# AQM_with_esp32.net
KiCad netlist of a schematic drawn in Altium Designer
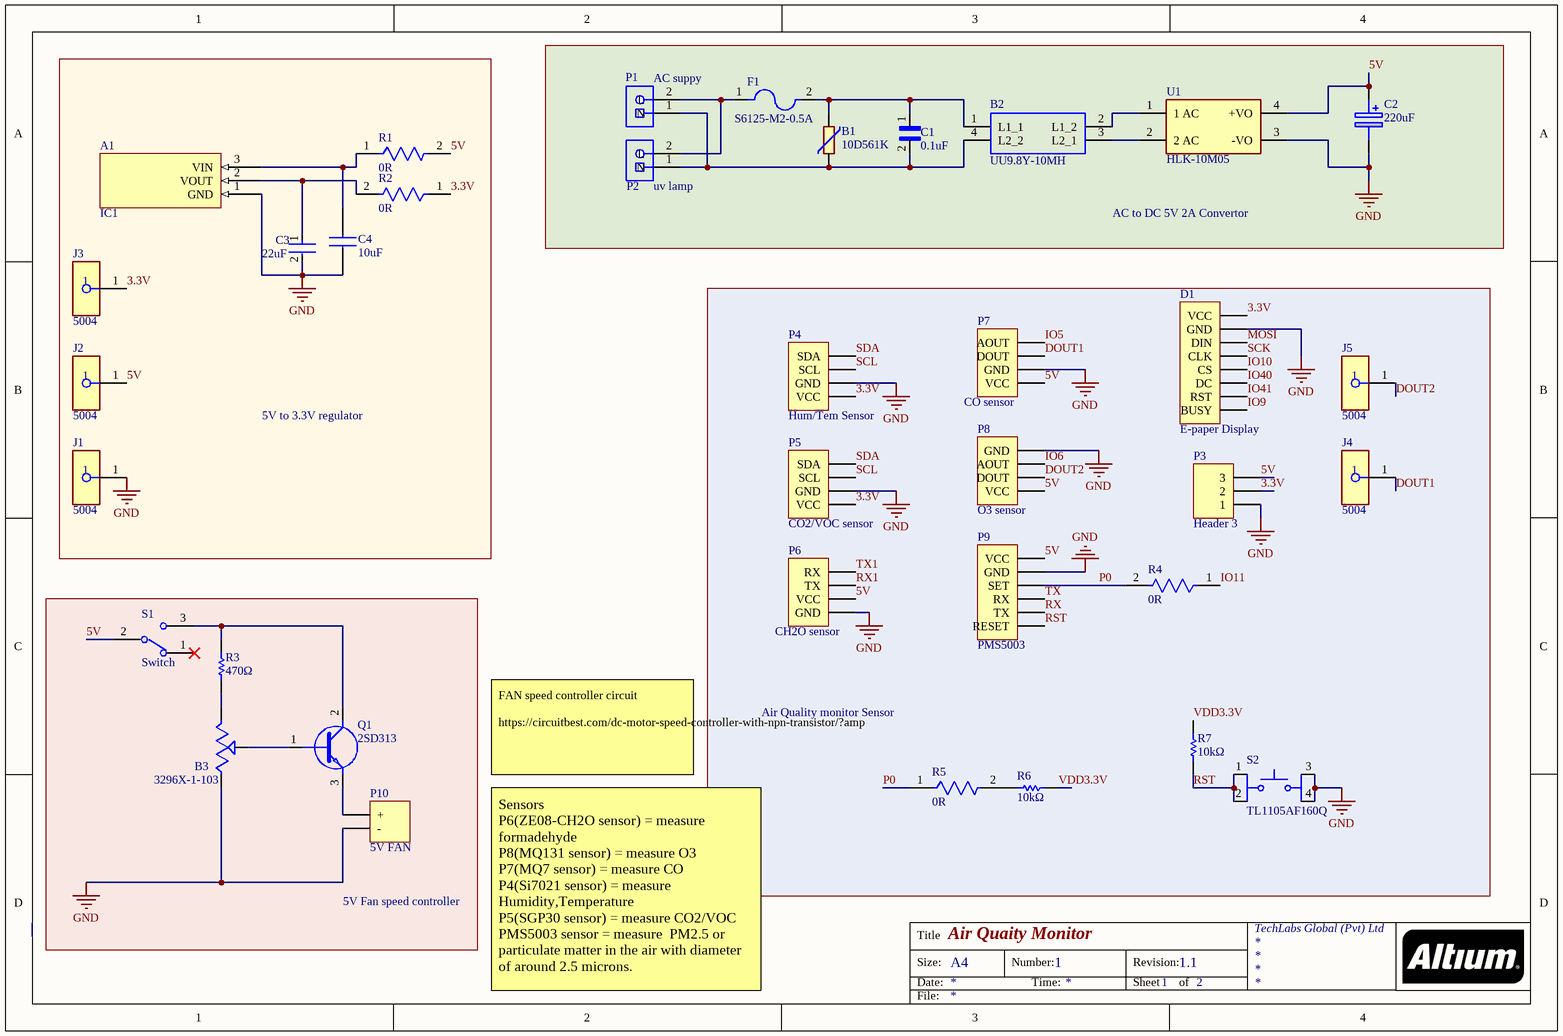
[diagram p0: AQM with esp32.SchDoc]

(export (version "E")
  (design (tool "Eeschema 10.0.6"))
  (components
    (comp (ref "A1")
      (value "IC1")
      (footprint "SOT89-150P350X150-3N")
      (fields
        (field (name "MANUFACTURER") "YONGYUTAI")
        (field (name "MFR. PART #") "AMS1117-3.3")
        (field (name "LCSC PART #") "C2904742")
      )
      (libsource (lib "AMS1117-3.3") (part "IC?"))
    )
    (comp (ref "B1")
      (value "10D561K")
      (footprint "10D561K")
      (description "920V 42.3J 180pF@1kHz 460V 350V 504V~616V 2.5kA Plugin Varistors ROHS")
      (fields (field (name "LCSC PART #") "C113236") (field (name "MANUFACTURER") "Hongzhi Elec"))
      (libsource (lib "10D561K") (part "10D561K"))
    )
    (comp (ref "B2")
      (value "UU9.8Y-10MH")
      (footprint "UU98Y10MH")
      (description "10mH@1kHz 1.2Ω 2 500mA 50V Plugin Common Mode Filters ROHS")
      (fields
        (field (name "MANUFACTURER") "FH (Guangdong Fenghua Advanced Tech)")
        (field (name "LCSC PART #") "C75192")
      )
      (libsource (lib "UU9.8Y-10MH") (part "UU9.8Y-10MH"))
    )
    (comp (ref "B3")
      (value "3296X-1-103")
      (footprint "3296X1223LF")
      (description "±10% 10kΩ Plugin Variable Resistors/Potentiometers ROHS")
      (fields
        (field (name "LCSC PART #") "C118955")
        (field (name "MANUFACTURER") "BOCHEN(Chengdu Guosheng Tech)")
      )
      (libsource (lib "3296X-1-103") (part "3296X-1-103"))
    )
    (comp (ref "C1")
      (value "0.1uF")
      (footprint "MPX-104K275VAC-C-D2")
      (description "X2 100nF ±10% 275V Plugin,P=15mm Suppression Capacitors ROHS")
      (fields (field (name "LCSC PART #") "C914484") (field (name "MANUFACTURER") "NDF"))
      (libsource (lib "X2-104K-275VAC") (part "MPX-104K275VAC-C-D2"))
    )
    (comp (ref "C2")
      (value "220uF")
      (footprint "CAPAE830X1050N")
      (fields
        (field (name "MANUFACTURER") "Nichicon")
        (field (name "MFR. PART #") "UUR1C221MNL1GS")
        (field (name "LCSC PART #") "C445237")
      )
      (libsource (lib "UUR1C221MNL1GS") (part "UUR1C221MNL1GS"))
    )
    (comp (ref "C3")
      (value "22uF")
      (footprint "FP-GRM219-0_2-0_15-IPC_A")
      (description "Chip Multilayer Ceramic Capacitors for General Purpose, 0805, 22uF, X5R, 15%, 20%, 16V")
      (fields (field (name "MFR. PART #") "GRM219R61C226ME15L") (field (name "LCSC PART #") "C162295"))
      (libsource (lib "Altium Content Vault") (part "b4654b650e69147ec39a6b967a45e02"))
    )
    (comp (ref "C4")
      (value "10uF")
      (footprint "CL05A106MQ5NUNC")
      (description "6.3V 10uF X5R ±20% 0402 Multilayer Ceramic Capacitors MLCC - SMD/SMT ROHS")
      (fields
        (field (name "MANUFACTURER") "Samsung Electro-Mechanics")
        (field (name "MFR. PART #") "CL05A106MQ5NUNC")
      )
      (libsource (lib "CL05A106MQ5NUNC") (part "CL05A106MQ5NUNC"))
    )
    (comp (ref "D1")
      (value "E-paper Display")
      (footprint "HDR1X8")
      (description "Header, 8-Pin")
      (fields (field (name "PUBLISHER") "Altium Limited"))
      (libsource (lib "Miscellaneous Connectors") (part "Header 8"))
    )
    (comp (ref "F1")
      (value "S6125-M2-0.5A")
      (footprint "CAPC6125X25N")
      (description "SMD Fuses ROHS")
      (fields (field (name "LCSC PART #") "C845172") (field (name "MANUFACTURER") "SART(Nanjing Sart Tech)"))
      (libsource (lib "S6125-M2-0.5A") (part "S6125-M2-0.5A"))
    )
    (comp (ref "J1")
      (value "5004")
      (footprint "FP-5004-MFG")
      (description "PC TEST POINT MINIATURE YELLOW")
      (fields (field (name "MANUFACTURER") "Keystone") (field (name "LCSC PART #") "C2906762"))
      (libsource (lib "Altium Content Vault") (part "98815daf2f2c152b0c43f5ab9800df6"))
    )
    (comp (ref "J2")
      (value "5004")
      (footprint "FP-5004-MFG")
      (description "PC TEST POINT MINIATURE YELLOW")
      (fields (field (name "MANUFACTURER") "Keystone") (field (name "LCSC PART #") "C2906762"))
      (libsource (lib "Altium Content Vault") (part "98815daf2f2c152b0c43f5ab9800df6"))
    )
    (comp (ref "J3")
      (value "5004")
      (footprint "FP-5004-MFG")
      (description "PC TEST POINT MINIATURE YELLOW")
      (fields (field (name "MANUFACTURER") "Keystone") (field (name "LCSC PART #") "C2906762"))
      (libsource (lib "Altium Content Vault") (part "98815daf2f2c152b0c43f5ab9800df6"))
    )
    (comp (ref "J4")
      (value "5004")
      (footprint "FP-5004-MFG")
      (description "PC TEST POINT MINIATURE YELLOW")
      (fields (field (name "MANUFACTURER") "Keystone") (field (name "LCSC PART #") "C2906762"))
      (libsource (lib "Altium Content Vault") (part "98815daf2f2c152b0c43f5ab9800df6"))
    )
    (comp (ref "J5")
      (value "5004")
      (footprint "FP-5004-MFG")
      (description "PC TEST POINT MINIATURE YELLOW")
      (fields (field (name "MANUFACTURER") "Keystone") (field (name "LCSC PART #") "C2906762"))
      (libsource (lib "Altium Content Vault") (part "98815daf2f2c152b0c43f5ab9800df6"))
    )
    (comp (ref "P1")
      (value "AC suppy")
      (footprint "PHOE-1729128-2_V")
      (description "13.5A 400V Green Straight pin 5.08mm 1 2 Plugin,P=5.08mm Screw terminal ROHS")
      (fields (field (name "MFR. PART #") "1729128") (field (name "LCSC PART #") "C91153"))
      (libsource (lib "Altium Content Vault") (part "CN-2P-F-R2"))
    )
    (comp (ref "P2")
      (value "uv lamp")
      (footprint "PHOE-1729128-2_V")
      (description "13.5A 400V Green Straight pin 5.08mm 1 2 Plugin,P=5.08mm Screw terminal ROHS")
      (fields (field (name "MFR. PART #") "1729128") (field (name "LCSC PART #") "C91153"))
      (libsource (lib "Altium Content Vault") (part "CN-2P-F-R2"))
    )
    (comp (ref "P3")
      (value "Header 3")
      (footprint "HDR1X3")
      (description "Header, 3-Pin")
      (fields (field (name "PUBLISHER") "Altium Limited"))
      (libsource (lib "Miscellaneous Connectors") (part "Header 3"))
    )
    (comp (ref "P4")
      (value "Hum/Tem Sensor")
      (footprint "HDR1X4")
      (description "Si7021 Header, 4-Pin")
      (libsource (lib "Miscellaneous Connectors") (part "Header 4"))
    )
    (comp (ref "P5")
      (value "CO2/VOC sensor")
      (footprint "HDR1X4")
      (description "SGP30 Header, 4-Pin")
      (fields (field (name "PUBLISHER") "Altium Limited"))
      (libsource (lib "Miscellaneous Connectors") (part "Header 4"))
    )
    (comp (ref "P6")
      (value "CH2O sensor")
      (footprint "HDR1X4")
      (description "- Sensor Modules ROHS")
      (fields
        (field (name "MFR. PART #") "ZE08-CH2O")
        (field (name "MANUFACTURER") "Zhengzhou Winsen Elec Tech")
      )
      (libsource (lib "") (part "Header 4_1"))
    )
    (comp (ref "P7")
      (value "CO sensor")
      (footprint "HDR1X4")
      (description "MQ7 Header, 4-Pin")
      (fields (field (name "PUBLISHER") "Altium Limited"))
      (libsource (lib "") (part "Header 4_2"))
    )
    (comp (ref "P8")
      (value "O3 sensor")
      (footprint "HDR1X4")
      (description "MQ131 Header, 4-Pin")
      (fields (field (name "PUBLISHER") "Altium Limited"))
      (libsource (lib "") (part "Header 4_3"))
    )
    (comp (ref "P9")
      (value "PMS5003")
      (footprint "HDR1X6")
      (description "PMS5003 Sensor Modules ROHS")
      (fields (field (name "LCSC PART #") "C91431") (field (name "MANUFACTURER") "Beijing Plantower"))
      (libsource (lib "Miscellaneous Connectors") (part "Header 6"))
    )
    (comp (ref "P10")
      (value "5V FAN")
      (footprint "HDR1X2")
      (description "Header, 2-Pin")
      (fields (field (name "PUBLISHER") "Altium Limited"))
      (libsource (lib "Miscellaneous Connectors") (part "Header 2"))
    )
    (comp (ref "Q1")
      (value "2SD313")
      (footprint "TO304P498X1010X2089-3P")
      (description "NPN Transistor, TO-220")
      (fields
        (field (name "LCSC PART #") "C3031919")
        (field (name "MANUFACTURER") "Jiangsu Changjing Electronics Technology Co., Ltd.")
      )
      (libsource (lib "2SD313") (part "2SD313"))
    )
    (comp (ref "R1")
      (value "0R")
      (footprint "FP-RC0402-0_4-IPC_A")
      (description "RES SMD 0 OHM JUMPER 1/16W 0402")
      (fields (field (name "MANUFACTURER") "Yageo") (field (name "LCSC PART #") "C106231"))
      (libsource (lib "Altium Content Vault") (part "1029c3af85768c4190bb7ad29bc67b5"))
    )
    (comp (ref "R2")
      (value "0R")
      (footprint "FP-RC0402-0_4-IPC_A")
      (description "RES SMD 0 OHM JUMPER 1/16W 0402")
      (fields (field (name "MANUFACTURER") "Yageo") (field (name "LCSC PART #") "C106231"))
      (libsource (lib "Altium Content Vault") (part "1029c3af85768c4190bb7ad29bc67b5"))
    )
    (comp (ref "R3")
      (value "470Ω")
      (footprint "RESC1608X55X25LL10T15")
      (fields
        (field (name "LCSC PART #") "C114669")
        (field (name "MFR. PART #") "RC0603FR-07470RL")
        (field (name "MANUFACTURER") "YAGEO")
      )
      (libsource (lib "Altium Content Vault") (part "RES-2"))
    )
    (comp (ref "R4")
      (value "0R")
      (footprint "FP-RC0402-0_4-IPC_A")
      (description "RES SMD 0 OHM JUMPER 1/16W 0402")
      (fields (field (name "MANUFACTURER") "Yageo") (field (name "LCSC PART #") "C106231"))
      (libsource (lib "Altium Content Vault") (part "1029c3af85768c4190bb7ad29bc67b5"))
    )
    (comp (ref "R5")
      (value "0R")
      (footprint "FP-RC0402-0_4-IPC_A")
      (description "RES SMD 0 OHM JUMPER 1/16W 0402")
      (fields (field (name "MANUFACTURER") "Yageo") (field (name "LCSC PART #") "C106231"))
      (libsource (lib "Altium Content Vault") (part "1029c3af85768c4190bb7ad29bc67b5"))
    )
    (comp (ref "R6")
      (value "10kΩ")
      (footprint "RESC1005X40X25LL05T10")
      (fields
        (field (name "MFR. PART #") "RC0402FR-0710KL")
        (field (name "MANUFACTURER") "YAGEO")
        (field (name "LCSC PART #") "C60490")
      )
      (libsource (lib "Altium Content Vault") (part "RES"))
    )
    (comp (ref "R7")
      (value "10kΩ")
      (footprint "RESC1005X40X25LL05T10")
      (fields
        (field (name "MFR. PART #") "RC0402FR-0710KL")
        (field (name "MANUFACTURER") "YAGEO")
        (field (name "LCSC PART #") "C60490")
      )
      (libsource (lib "Altium Content Vault") (part "RES"))
    )
    (comp (ref "S1")
      (value "Switch")
      (footprint "SK3245SL1A")
      (fields
        (field (name "MANUFACTURER") "XKB Connectivity")
        (field (name "MFR. PART #") "SK-3245S-L1-A")
        (field (name "LCSC PART #") "C405951")
      )
      (libsource (lib "SK-3245S-L1-A") (part "SK-3245S-L1-A"))
    )
    (comp (ref "S2")
      (value "TL1105AF160Q")
      (footprint "TL1105AF160Q")
      (description "6mm 1.4mm Round Button 50mA Straight 6mm SPST 12V Plugin,6x6mm Tactile Switches ROHS")
      (fields (field (name "MANUFACTURER") "E-Switch") (field (name "LCSC PART #") "C273465"))
      (libsource (lib "TL1105AF160Q") (part "TL1105AF160Q"))
    )
    (comp (ref "U1")
      (value "HLK-10M05")
      (footprint "FP-HLK-10M05-MFG")
      (description "5V 2A 90VAC~265VAC 1 120V~350V Isolated Regulated 10W AC-DC 80% Plugin Power Modules ROHS")
      (fields (field (name "MANUFACTURER") "HI-LINK") (field (name "LCSC PART #") "C403745"))
      (libsource (lib "Altium Content Vault") (part "a65b17ccb3a75dffb3c3e849074403b"))
    )
  )
  (nets
    (net (code "1") (name "/3.3V") (class "Default")
      (node (ref "D1") (pin "8") (pinfunction "VCC_8") (pintype "passive"))
      (node (ref "J3") (pin "1") (pinfunction "1_1") (pintype "passive"))
      (node (ref "P3") (pin "2") (pinfunction "2_2") (pintype "passive"))
      (node (ref "P4") (pin "1") (pinfunction "VCC_1") (pintype "passive"))
      (node (ref "P5") (pin "1") (pinfunction "VCC_1") (pintype "passive"))
      (node (ref "R2") (pin "1") (pinfunction "1_1") (pintype "passive"))
    )
    (net (code "2") (name "/5V") (class "Default")
      (node (ref "C2") (pin "1") (pinfunction "+_1") (pintype "passive"))
      (node (ref "J2") (pin "1") (pinfunction "1_1") (pintype "passive"))
      (node (ref "P3") (pin "3") (pinfunction "3_3") (pintype "passive"))
      (node (ref "P6") (pin "2") (pinfunction "VCC_2") (pintype "passive"))
      (node (ref "P7") (pin "1") (pinfunction "VCC_1") (pintype "passive"))
      (node (ref "P8") (pin "1") (pinfunction "VCC_1") (pintype "passive"))
      (node (ref "P9") (pin "6") (pinfunction "VCC_6") (pintype "passive"))
      (node (ref "R1") (pin "2") (pinfunction "2_2") (pintype "passive"))
      (node (ref "S1") (pin "2") (pinfunction "2_2") (pintype "passive"))
      (node (ref "U1") (pin "4") (pinfunction "+VO_4") (pintype "power_in"))
    )
    (net (code "3") (name "/DOUT1") (class "Default")
      (node (ref "J4") (pin "1") (pinfunction "1_1") (pintype "passive"))
      (node (ref "P7") (pin "3") (pinfunction "DOUT_3") (pintype "passive"))
    )
    (net (code "4") (name "/DOUT2") (class "Default")
      (node (ref "J5") (pin "1") (pinfunction "1_1") (pintype "passive"))
      (node (ref "P8") (pin "2") (pinfunction "DOUT_2") (pintype "passive"))
    )
    (net (code "5") (name "/IO5") (class "Default")
      (node (ref "P7") (pin "4") (pinfunction "AOUT_4") (pintype "passive"))
    )
    (net (code "6") (name "/IO6") (class "Default")
      (node (ref "P8") (pin "3") (pinfunction "AOUT_3") (pintype "passive"))
    )
    (net (code "7") (name "/IO9") (class "Default")
      (node (ref "D1") (pin "1") (pinfunction "BUSY_1") (pintype "passive"))
    )
    (net (code "8") (name "/IO10") (class "Default")
      (node (ref "D1") (pin "4") (pinfunction "CS_4") (pintype "passive"))
    )
    (net (code "9") (name "/IO11") (class "Default")
      (node (ref "R4") (pin "1") (pinfunction "1_1") (pintype "passive"))
    )
    (net (code "10") (name "/IO40") (class "Default")
      (node (ref "D1") (pin "3") (pinfunction "DC_3") (pintype "passive"))
    )
    (net (code "11") (name "/IO41") (class "Default")
      (node (ref "D1") (pin "2") (pinfunction "RST_2") (pintype "passive"))
    )
    (net (code "12") (name "/MOSI") (class "Default")
      (node (ref "D1") (pin "6") (pinfunction "DIN_6") (pintype "passive"))
    )
    (net (code "13") (name "/P0") (class "Default")
      (node (ref "P9") (pin "4") (pinfunction "SET_4") (pintype "passive"))
      (node (ref "R4") (pin "2") (pinfunction "2_2") (pintype "passive"))
      (node (ref "R5") (pin "1") (pinfunction "1_1") (pintype "passive"))
    )
    (net (code "14") (name "/RST") (class "Default")
      (node (ref "P9") (pin "1") (pinfunction "RESET_1") (pintype "passive"))
      (node (ref "R7") (pin "2") (pinfunction "2_2") (pintype "passive"))
      (node (ref "S2") (pin "1") (pinfunction "1_1") (pintype "passive"))
      (node (ref "S2") (pin "2") (pinfunction "2_2") (pintype "passive"))
    )
    (net (code "15") (name "/RX") (class "Default")
      (node (ref "P9") (pin "2") (pinfunction "TX_2") (pintype "passive"))
    )
    (net (code "16") (name "/RX1") (class "Default")
      (node (ref "P6") (pin "3") (pinfunction "TX_3") (pintype "passive"))
    )
    (net (code "17") (name "/SCK") (class "Default")
      (node (ref "D1") (pin "5") (pinfunction "CLK_5") (pintype "passive"))
    )
    (net (code "18") (name "/SCL") (class "Default")
      (node (ref "P4") (pin "3") (pinfunction "SCL_3") (pintype "passive"))
      (node (ref "P5") (pin "3") (pinfunction "SCL_3") (pintype "passive"))
    )
    (net (code "19") (name "/SDA") (class "Default")
      (node (ref "P4") (pin "4") (pinfunction "SDA_4") (pintype "passive"))
      (node (ref "P5") (pin "4") (pinfunction "SDA_4") (pintype "passive"))
    )
    (net (code "20") (name "/TX") (class "Default")
      (node (ref "P9") (pin "3") (pinfunction "RX_3") (pintype "passive"))
    )
    (net (code "21") (name "/TX1") (class "Default")
      (node (ref "P6") (pin "4") (pinfunction "RX_4") (pintype "passive"))
    )
    (net (code "22") (name "/VDD3.3V") (class "Default")
      (node (ref "R6") (pin "1") (pinfunction "1_1") (pintype "passive"))
      (node (ref "R7") (pin "1") (pinfunction "1_1") (pintype "passive"))
    )
    (net (code "23") (name "GND") (class "Default")
      (node (ref "A1") (pin "1") (pinfunction "GND_1") (pintype "input"))
      (node (ref "B3") (pin "1") (pinfunction "A_1") (pintype "passive"))
      (node (ref "C2") (pin "2") (pinfunction "-_2") (pintype "passive"))
      (node (ref "C3") (pin "2") (pinfunction "2_2") (pintype "passive"))
      (node (ref "C4") (pin "1") (pinfunction "1_1") (pintype "passive"))
      (node (ref "D1") (pin "7") (pinfunction "GND_7") (pintype "passive"))
      (node (ref "J1") (pin "1") (pinfunction "1_1") (pintype "passive"))
      (node (ref "P10") (pin "2") (pinfunction "-_2") (pintype "passive"))
      (node (ref "P3") (pin "1") (pinfunction "1_1") (pintype "passive"))
      (node (ref "P4") (pin "2") (pinfunction "GND_2") (pintype "passive"))
      (node (ref "P5") (pin "2") (pinfunction "GND_2") (pintype "passive"))
      (node (ref "P6") (pin "1") (pinfunction "GND_1") (pintype "passive"))
      (node (ref "P7") (pin "2") (pinfunction "GND_2") (pintype "passive"))
      (node (ref "P8") (pin "4") (pinfunction "GND_4") (pintype "passive"))
      (node (ref "P9") (pin "5") (pinfunction "GND_5") (pintype "passive"))
      (node (ref "S2") (pin "3") (pinfunction "3_3") (pintype "passive"))
      (node (ref "S2") (pin "4") (pinfunction "4_4") (pintype "passive"))
      (node (ref "U1") (pin "3") (pinfunction "-VO_3") (pintype "power_in"))
    )
    (net (code "24") (name "Net-(A1-VIN)") (class "Default")
      (node (ref "A1") (pin "3") (pinfunction "VIN_3") (pintype "input"))
      (node (ref "C4") (pin "2") (pinfunction "2_2") (pintype "passive"))
      (node (ref "R1") (pin "1") (pinfunction "1_1") (pintype "passive"))
    )
    (net (code "25") (name "Net-(A1-VOUT)") (class "Default")
      (node (ref "A1") (pin "2") (pinfunction "VOUT_2") (pintype "input"))
      (node (ref "C3") (pin "1") (pinfunction "1_1") (pintype "passive"))
      (node (ref "R2") (pin "2") (pinfunction "2_2") (pintype "passive"))
    )
    (net (code "26") (name "Net-(B2-L1_1)") (class "Default")
      (node (ref "B1") (pin "1") (pinfunction "1_1") (pintype "passive"))
      (node (ref "B2") (pin "1") (pinfunction "L1_1_1") (pintype "passive"))
      (node (ref "C1") (pin "1") (pinfunction "1_1") (pintype "passive"))
      (node (ref "F1") (pin "2") (pinfunction "2_2") (pintype "passive"))
    )
    (net (code "27") (name "Net-(B2-L1_2)") (class "Default")
      (node (ref "B2") (pin "2") (pinfunction "L1_2_2") (pintype "passive"))
      (node (ref "U1") (pin "1") (pinfunction "1_AC_1") (pintype "passive"))
    )
    (net (code "28") (name "Net-(B2-L2_1)") (class "Default")
      (node (ref "B2") (pin "3") (pinfunction "L2_1_3") (pintype "passive"))
      (node (ref "U1") (pin "2") (pinfunction "2_AC_2") (pintype "passive"))
    )
    (net (code "29") (name "Net-(B2-L2_2)") (class "Default")
      (node (ref "B1") (pin "2") (pinfunction "2_2") (pintype "passive"))
      (node (ref "B2") (pin "4") (pinfunction "L2_2_4") (pintype "passive"))
      (node (ref "C1") (pin "2") (pinfunction "2_2") (pintype "passive"))
      (node (ref "P1") (pin "1") (pinfunction "N_1") (pintype "passive"))
      (node (ref "P2") (pin "1") (pinfunction "N_1") (pintype "passive"))
    )
    (net (code "30") (name "Net-(B3-B)") (class "Default")
      (node (ref "B3") (pin "2") (pinfunction "B_2") (pintype "passive"))
      (node (ref "Q1") (pin "1") (pinfunction "B_1") (pintype "passive"))
    )
    (net (code "31") (name "Net-(B3-C)") (class "Default")
      (node (ref "B3") (pin "3") (pinfunction "C_3") (pintype "passive"))
      (node (ref "R3") (pin "1") (pinfunction "1_1") (pintype "passive"))
    )
    (net (code "32") (name "Net-(P1-L)") (class "Default")
      (node (ref "F1") (pin "1") (pinfunction "1_1") (pintype "passive"))
      (node (ref "P1") (pin "2") (pinfunction "L_2") (pintype "passive"))
      (node (ref "P2") (pin "2") (pinfunction "L_2") (pintype "passive"))
    )
    (net (code "33") (name "Net-(P10-+)") (class "Default")
      (node (ref "P10") (pin "1") (pinfunction "+_1") (pintype "passive"))
      (node (ref "Q1") (pin "3") (pinfunction "E_3") (pintype "passive"))
    )
    (net (code "34") (name "Net-(Q1-C)") (class "Default")
      (node (ref "Q1") (pin "2") (pinfunction "C_2") (pintype "passive"))
      (node (ref "R3") (pin "2") (pinfunction "2_2") (pintype "passive"))
      (node (ref "S1") (pin "3") (pinfunction "3_3") (pintype "passive"))
    )
    (net (code "35") (name "Net-(R5-Pad2)") (class "Default")
      (node (ref "R5") (pin "2") (pinfunction "2_2") (pintype "passive"))
      (node (ref "R6") (pin "2") (pinfunction "2_2") (pintype "passive"))
    )
    (net (code "36") (name "unconnected-(S1-Pad1)") (class "Default")
      (node (ref "S1") (pin "1") (pinfunction "1_1") (pintype "passive+no_connect"))
    )
  )
)
